# eeZeeSwitch.net
KiCad netlist of a schematic drawn in EAGLE
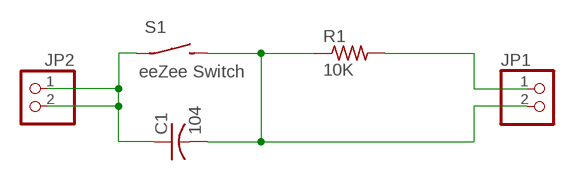
[diagram p0: schematic, sheet 1]

(export (version "E")
  (design (tool "Eeschema 10.0.6"))
  (components
    (comp (ref "C1")
      (value "104")
      (footprint "eagle-import:C0603")
      (libsource (lib "eagle-import") (part "C-USC0603"))
    )
    (comp (ref "JP1")
      (value "PINHD-1X02_2.54-S")
      (footprint "eagle-import:1X02-S")
      (libsource (lib "eagle-import") (part "PINHD-1X02_2.54-S"))
    )
    (comp (ref "JP2")
      (value "PINHD-1X02_2.54-S")
      (footprint "eagle-import:1X02-S")
      (libsource (lib "eagle-import") (part "PINHD-1X02_2.54-S"))
    )
    (comp (ref "R1")
      (value "10K")
      (footprint "eagle-import:R0603")
      (libsource (lib "eagle-import") (part "R-US_R0603"))
    )
    (comp (ref "S1")
      (value "eeZee Switch")
      (footprint "eagle-import:6MMTACTILE_RECT")
      (libsource (lib "eagle-import") (part "SPST_TAC_RECT1"))
    )
  )
  (nets
    (net (code "1") (name "Net-(JP1-Pad1)") (class "Default")
      (node (ref "JP1") (pin "1") (pinfunction "1_1") (pintype "passive"))
      (node (ref "R1") (pin "2") (pinfunction "2_2") (pintype "passive"))
    )
    (net (code "2") (name "Net-(S1-P)") (class "Default")
      (node (ref "C1") (pin "1") (pinfunction "1_1") (pintype "passive"))
      (node (ref "JP2") (pin "1") (pinfunction "1_1") (pintype "passive"))
      (node (ref "JP2") (pin "2") (pinfunction "2_2") (pintype "passive"))
      (node (ref "S1") (pin "P$1") (pinfunction "P_P$1") (pintype "passive"))
    )
    (net (code "3") (name "Net-(S1-S)") (class "Default")
      (node (ref "C1") (pin "2") (pinfunction "2_2") (pintype "passive"))
      (node (ref "JP1") (pin "2") (pinfunction "2_2") (pintype "passive"))
      (node (ref "R1") (pin "1") (pinfunction "1_1") (pintype "passive"))
      (node (ref "S1") (pin "P$2") (pinfunction "S_P$2") (pintype "passive"))
    )
  )
)
